# PCB_Nano.net
KiCad netlist of a schematic drawn in EAGLE
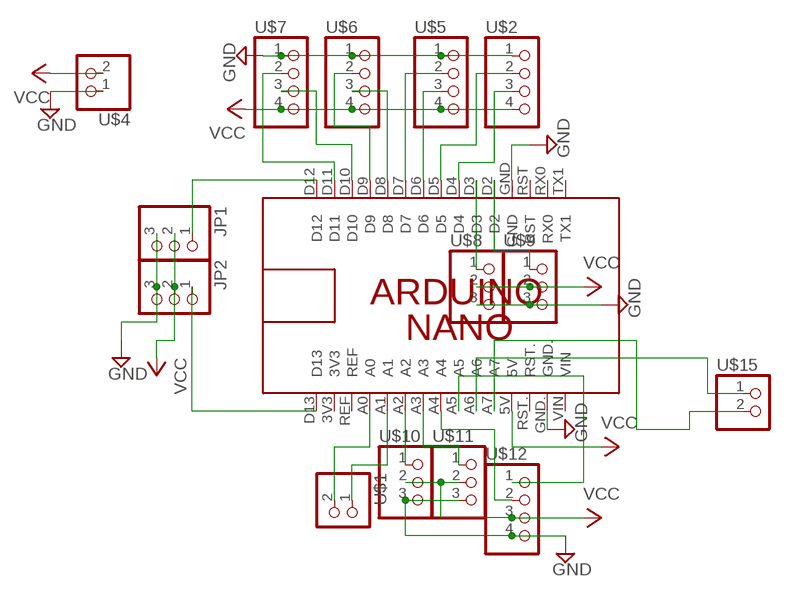
[diagram p0: schematic, sheet 1]

(export (version "E")
  (design (tool "Eeschema 10.0.6"))
  (components
    (comp (ref "JP1")
      (value "PINHD-1X3")
      (footprint "eagle-import:1X03")
      (libsource (lib "eagle-import") (part "PINHD-1X3"))
    )
    (comp (ref "JP2")
      (value "PINHD-1X3")
      (footprint "eagle-import:1X03")
      (libsource (lib "eagle-import") (part "PINHD-1X3"))
    )
    (comp (ref "PCB1")
      (value "ARDUINO_NANO_SHIELD")
      (footprint "eagle-import:ARDUINO_NANO_W_HEADER_&_SOCKET")
      (libsource (lib "eagle-import") (part "ARDUINO_NANO_SHIELD"))
    )
    (comp (ref "U$1")
      (value "PINHD-1X2")
      (footprint "eagle-import:1X02")
      (libsource (lib "eagle-import") (part "PINHD-1X2"))
    )
    (comp (ref "U$2")
      (value "PINHD-1X4")
      (footprint "eagle-import:1X04")
      (libsource (lib "eagle-import") (part "PINHD-1X4"))
    )
    (comp (ref "U$4")
      (value "TERMINALBLOCK_1X2-5.0MM")
      (footprint "eagle-import:TERMINALBLOCK_1X2-5.0MM")
      (libsource (lib "eagle-import") (part "TERMINALBLOCK_1X2-5.0MM"))
    )
    (comp (ref "U$5")
      (value "PINHD-1X4")
      (footprint "eagle-import:1X04")
      (libsource (lib "eagle-import") (part "PINHD-1X4"))
    )
    (comp (ref "U$6")
      (value "PINHD-1X4")
      (footprint "eagle-import:1X04")
      (libsource (lib "eagle-import") (part "PINHD-1X4"))
    )
    (comp (ref "U$7")
      (value "PINHD-1X4")
      (footprint "eagle-import:1X04")
      (libsource (lib "eagle-import") (part "PINHD-1X4"))
    )
    (comp (ref "U$8")
      (value "PINHD-1X3")
      (footprint "eagle-import:1X03")
      (libsource (lib "eagle-import") (part "PINHD-1X3"))
    )
    (comp (ref "U$9")
      (value "PINHD-1X3")
      (footprint "eagle-import:1X03")
      (libsource (lib "eagle-import") (part "PINHD-1X3"))
    )
    (comp (ref "U$10")
      (value "PINHD-1X3")
      (footprint "eagle-import:1X03")
      (libsource (lib "eagle-import") (part "PINHD-1X3"))
    )
    (comp (ref "U$11")
      (value "PINHD-1X3")
      (footprint "eagle-import:1X03")
      (libsource (lib "eagle-import") (part "PINHD-1X3"))
    )
    (comp (ref "U$12")
      (value "PINHD-1X4")
      (footprint "eagle-import:1X04")
      (libsource (lib "eagle-import") (part "PINHD-1X4"))
    )
    (comp (ref "U$15")
      (value "PINHD-1X2")
      (footprint "eagle-import:1X02")
      (libsource (lib "eagle-import") (part "PINHD-1X2"))
    )
  )
  (nets
    (net (code "1") (name "GND") (class "Default")
      (node (ref "JP1") (pin "3") (pinfunction "3_3") (pintype "passive"))
      (node (ref "JP2") (pin "3") (pinfunction "3_3") (pintype "passive"))
      (node (ref "PCB1") (pin "GND") (pinfunction "GND_GND") (pintype "bidirectional"))
      (node (ref "PCB1") (pin "GND.") (pinfunction "GND._GND.") (pintype "bidirectional"))
      (node (ref "U$10") (pin "3") (pinfunction "3_3") (pintype "passive"))
      (node (ref "U$11") (pin "3") (pinfunction "3_3") (pintype "passive"))
      (node (ref "U$12") (pin "4") (pinfunction "4_4") (pintype "passive"))
      (node (ref "U$2") (pin "1") (pinfunction "1_1") (pintype "passive"))
      (node (ref "U$4") (pin "1") (pinfunction "1_1") (pintype "passive"))
      (node (ref "U$5") (pin "1") (pinfunction "1_1") (pintype "passive"))
      (node (ref "U$6") (pin "1") (pinfunction "1_1") (pintype "passive"))
      (node (ref "U$7") (pin "1") (pinfunction "1_1") (pintype "passive"))
      (node (ref "U$8") (pin "3") (pinfunction "3_3") (pintype "passive"))
      (node (ref "U$9") (pin "3") (pinfunction "3_3") (pintype "passive"))
    )
    (net (code "2") (name "Net-(JP1-Pad1)") (class "Default")
      (node (ref "JP1") (pin "1") (pinfunction "1_1") (pintype "passive"))
      (node (ref "PCB1") (pin "D12") (pinfunction "D12_D12") (pintype "bidirectional"))
    )
    (net (code "3") (name "Net-(JP2-Pad1)") (class "Default")
      (node (ref "JP2") (pin "1") (pinfunction "1_1") (pintype "passive"))
      (node (ref "PCB1") (pin "D13") (pinfunction "D13_D13") (pintype "bidirectional"))
    )
    (net (code "4") (name "Net-(PCB1-PadA0)") (class "Default")
      (node (ref "PCB1") (pin "A0") (pinfunction "A0_A0") (pintype "bidirectional"))
      (node (ref "U$1") (pin "2") (pinfunction "2_2") (pintype "passive"))
    )
    (net (code "5") (name "Net-(PCB1-PadA1)") (class "Default")
      (node (ref "PCB1") (pin "A1") (pinfunction "A1_A1") (pintype "bidirectional"))
      (node (ref "U$1") (pin "1") (pinfunction "1_1") (pintype "passive"))
    )
    (net (code "6") (name "Net-(PCB1-PadA2)") (class "Default")
      (node (ref "PCB1") (pin "A2") (pinfunction "A2_A2") (pintype "bidirectional"))
      (node (ref "U$10") (pin "1") (pinfunction "1_1") (pintype "passive"))
    )
    (net (code "7") (name "Net-(PCB1-PadA3)") (class "Default")
      (node (ref "PCB1") (pin "A3") (pinfunction "A3_A3") (pintype "bidirectional"))
      (node (ref "U$11") (pin "1") (pinfunction "1_1") (pintype "passive"))
    )
    (net (code "8") (name "Net-(PCB1-PadA4)") (class "Default")
      (node (ref "PCB1") (pin "A4") (pinfunction "A4_A4") (pintype "bidirectional"))
      (node (ref "U$12") (pin "2") (pinfunction "2_2") (pintype "passive"))
    )
    (net (code "9") (name "Net-(PCB1-PadA5)") (class "Default")
      (node (ref "PCB1") (pin "A5") (pinfunction "A5_A5") (pintype "bidirectional"))
      (node (ref "U$12") (pin "1") (pinfunction "1_1") (pintype "passive"))
    )
    (net (code "10") (name "Net-(PCB1-PadA6)") (class "Default")
      (node (ref "PCB1") (pin "A6") (pinfunction "A6_A6") (pintype "bidirectional"))
      (node (ref "U$15") (pin "1") (pinfunction "1_1") (pintype "passive"))
    )
    (net (code "11") (name "Net-(PCB1-PadA7)") (class "Default")
      (node (ref "PCB1") (pin "A7") (pinfunction "A7_A7") (pintype "bidirectional"))
      (node (ref "U$15") (pin "2") (pinfunction "2_2") (pintype "passive"))
    )
    (net (code "12") (name "Net-(PCB1-PadD2)") (class "Default")
      (node (ref "PCB1") (pin "D2") (pinfunction "D2_D2") (pintype "bidirectional"))
      (node (ref "U$9") (pin "1") (pinfunction "1_1") (pintype "passive"))
    )
    (net (code "13") (name "Net-(PCB1-PadD3)") (class "Default")
      (node (ref "PCB1") (pin "D3") (pinfunction "D3_D3") (pintype "bidirectional"))
      (node (ref "U$8") (pin "1") (pinfunction "1_1") (pintype "passive"))
    )
    (net (code "14") (name "Net-(PCB1-PadD4)") (class "Default")
      (node (ref "PCB1") (pin "D4") (pinfunction "D4_D4") (pintype "bidirectional"))
      (node (ref "U$2") (pin "3") (pinfunction "3_3") (pintype "passive"))
    )
    (net (code "15") (name "Net-(PCB1-PadD5)") (class "Default")
      (node (ref "PCB1") (pin "D5") (pinfunction "D5_D5") (pintype "bidirectional"))
      (node (ref "U$2") (pin "2") (pinfunction "2_2") (pintype "passive"))
    )
    (net (code "16") (name "Net-(PCB1-PadD6)") (class "Default")
      (node (ref "PCB1") (pin "D6") (pinfunction "D6_D6") (pintype "bidirectional"))
      (node (ref "U$5") (pin "3") (pinfunction "3_3") (pintype "passive"))
    )
    (net (code "17") (name "Net-(PCB1-PadD7)") (class "Default")
      (node (ref "PCB1") (pin "D7") (pinfunction "D7_D7") (pintype "bidirectional"))
      (node (ref "U$5") (pin "2") (pinfunction "2_2") (pintype "passive"))
    )
    (net (code "18") (name "Net-(PCB1-PadD8)") (class "Default")
      (node (ref "PCB1") (pin "D8") (pinfunction "D8_D8") (pintype "bidirectional"))
      (node (ref "U$6") (pin "3") (pinfunction "3_3") (pintype "passive"))
    )
    (net (code "19") (name "Net-(PCB1-PadD9)") (class "Default")
      (node (ref "PCB1") (pin "D9") (pinfunction "D9_D9") (pintype "bidirectional"))
      (node (ref "U$6") (pin "2") (pinfunction "2_2") (pintype "passive"))
    )
    (net (code "20") (name "Net-(PCB1-PadD10)") (class "Default")
      (node (ref "PCB1") (pin "D10") (pinfunction "D10_D10") (pintype "bidirectional"))
      (node (ref "U$7") (pin "3") (pinfunction "3_3") (pintype "passive"))
    )
    (net (code "21") (name "Net-(PCB1-PadD11)") (class "Default")
      (node (ref "PCB1") (pin "D11") (pinfunction "D11_D11") (pintype "bidirectional"))
      (node (ref "U$7") (pin "2") (pinfunction "2_2") (pintype "passive"))
    )
    (net (code "22") (name "VCC") (class "Default")
      (node (ref "JP1") (pin "2") (pinfunction "2_2") (pintype "passive"))
      (node (ref "JP2") (pin "2") (pinfunction "2_2") (pintype "passive"))
      (node (ref "PCB1") (pin "5V") (pinfunction "5V_5V") (pintype "bidirectional"))
      (node (ref "U$10") (pin "2") (pinfunction "2_2") (pintype "passive"))
      (node (ref "U$11") (pin "2") (pinfunction "2_2") (pintype "passive"))
      (node (ref "U$12") (pin "3") (pinfunction "3_3") (pintype "passive"))
      (node (ref "U$2") (pin "4") (pinfunction "4_4") (pintype "passive"))
      (node (ref "U$4") (pin "2") (pinfunction "2_2") (pintype "passive"))
      (node (ref "U$5") (pin "4") (pinfunction "4_4") (pintype "passive"))
      (node (ref "U$6") (pin "4") (pinfunction "4_4") (pintype "passive"))
      (node (ref "U$7") (pin "4") (pinfunction "4_4") (pintype "passive"))
      (node (ref "U$8") (pin "2") (pinfunction "2_2") (pintype "passive"))
      (node (ref "U$9") (pin "2") (pinfunction "2_2") (pintype "passive"))
    )
    (net (code "23") (name "unconnected-(PCB1-Pad3V3)") (class "Default")
      (node (ref "PCB1") (pin "3V3") (pinfunction "3V3_3V3") (pintype "bidirectional"))
    )
    (net (code "24") (name "unconnected-(PCB1-PadREF)") (class "Default")
      (node (ref "PCB1") (pin "REF") (pinfunction "REF_REF") (pintype "bidirectional"))
    )
    (net (code "25") (name "unconnected-(PCB1-PadRST)") (class "Default")
      (node (ref "PCB1") (pin "RST") (pinfunction "RST_RST") (pintype "bidirectional"))
    )
    (net (code "26") (name "unconnected-(PCB1-PadRST.)") (class "Default")
      (node (ref "PCB1") (pin "RST.") (pinfunction "RST._RST.") (pintype "bidirectional"))
    )
    (net (code "27") (name "unconnected-(PCB1-PadRX0)") (class "Default")
      (node (ref "PCB1") (pin "RX0") (pinfunction "RX0_RX0") (pintype "bidirectional"))
    )
    (net (code "28") (name "unconnected-(PCB1-PadTX1)") (class "Default")
      (node (ref "PCB1") (pin "TX1") (pinfunction "TX1_TX1") (pintype "bidirectional"))
    )
    (net (code "29") (name "unconnected-(PCB1-PadVIN)") (class "Default")
      (node (ref "PCB1") (pin "VIN") (pinfunction "VIN_VIN") (pintype "bidirectional"))
    )
  )
)
